# rgb_and_irdistance.net
KiCad netlist of a schematic drawn in EAGLE
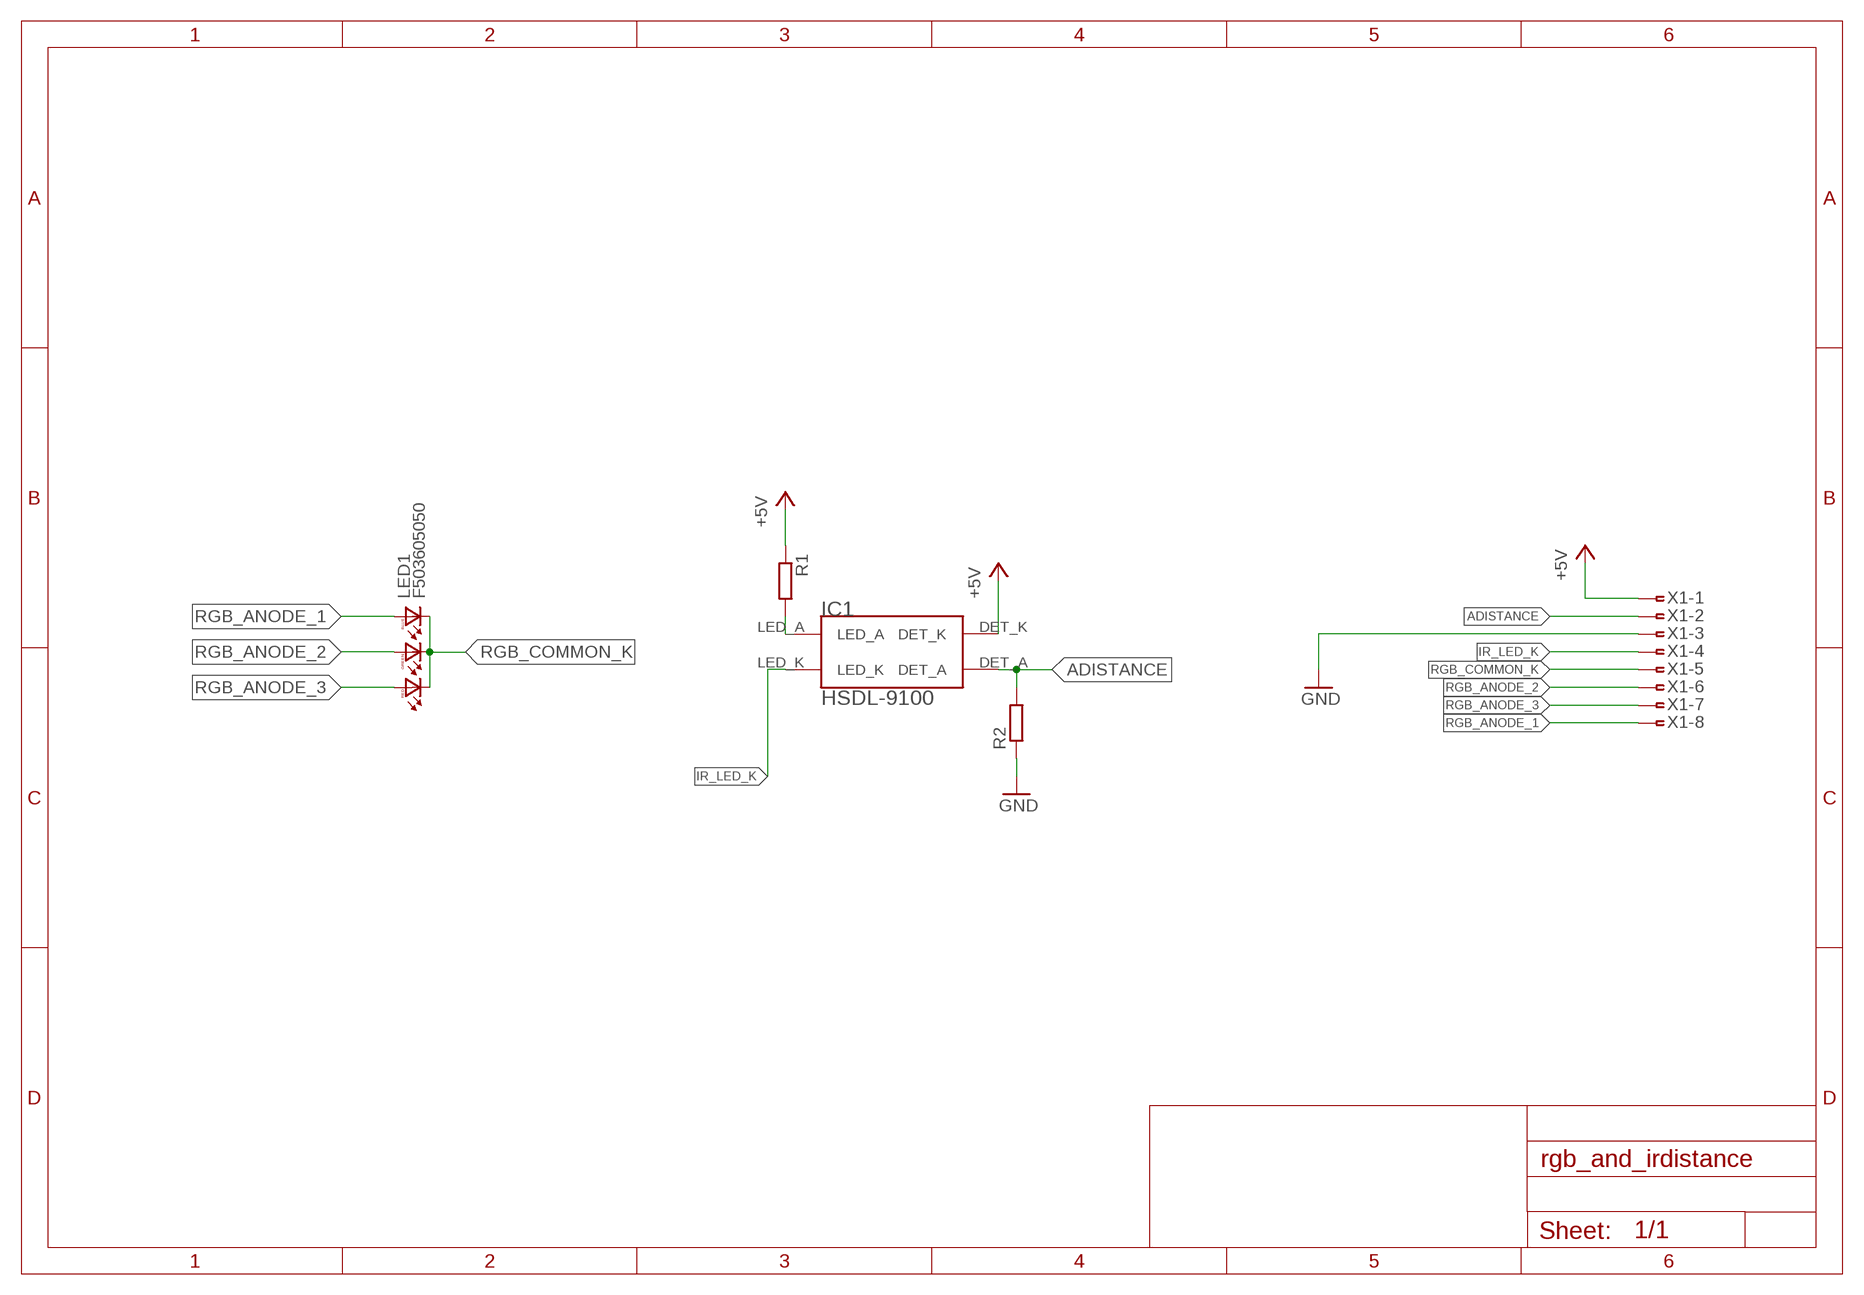
[diagram p0: schematic, sheet 1]

(export (version "E")
  (design (tool "Eeschema 10.0.6"))
  (components
    (comp (ref "IC1")
      (value "HSDL-9100")
      (footprint "eagle-import:HSDL-9100")
      (libsource (lib "eagle-import") (part "HSDL-9100"))
    )
    (comp (ref "LED1")
      (value "F503605050")
      (footprint "eagle-import:5050LED")
      (libsource (lib "eagle-import") (part "F503605050"))
    )
    (comp (ref "R1")
      (value "R-EU_M0805")
      (footprint "eagle-import:M0805")
      (libsource (lib "eagle-import") (part "R-EU_M0805"))
    )
    (comp (ref "R2")
      (value "R-EU_M0805")
      (footprint "eagle-import:M0805")
      (libsource (lib "eagle-import") (part "R-EU_M0805"))
    )
    (comp (ref "X1")
      (value "FTOP-8")
      (footprint "eagle-import:FTOP-8")
      (libsource (lib "eagle-import") (part "FTOP-8"))
    )
  )
  (nets
    (net (code "1") (name "+5V") (class "Default")
      (node (ref "IC1") (pin "DET_K") (pinfunction "DET_K_DET_K") (pintype "bidirectional"))
      (node (ref "R1") (pin "1") (pinfunction "1_1") (pintype "passive"))
      (node (ref "X1") (pin "1") (pinfunction "1_1") (pintype "passive"))
    )
    (net (code "2") (name "ADISTANCE") (class "Default")
      (node (ref "IC1") (pin "DET_A") (pinfunction "DET_A_DET_A") (pintype "bidirectional"))
      (node (ref "R2") (pin "2") (pinfunction "2_2") (pintype "passive"))
      (node (ref "X1") (pin "2") (pinfunction "1_2") (pintype "passive"))
    )
    (net (code "3") (name "GND") (class "Default")
      (node (ref "R2") (pin "1") (pinfunction "1_1") (pintype "passive"))
      (node (ref "X1") (pin "3") (pinfunction "1_3") (pintype "passive"))
    )
    (net (code "4") (name "IR_LED_K") (class "Default")
      (node (ref "IC1") (pin "LED_K") (pinfunction "LED_K_LED_K") (pintype "bidirectional"))
      (node (ref "X1") (pin "4") (pinfunction "1_4") (pintype "passive"))
    )
    (net (code "5") (name "Net-(IC1-PadLED_A)") (class "Default")
      (node (ref "IC1") (pin "LED_A") (pinfunction "LED_A_LED_A") (pintype "bidirectional"))
      (node (ref "R1") (pin "2") (pinfunction "2_2") (pintype "passive"))
    )
    (net (code "6") (name "RGB_ANODE_1") (class "Default")
      (node (ref "LED1") (pin "B1") (pinfunction "BA_B1") (pintype "passive"))
      (node (ref "X1") (pin "8") (pinfunction "1_8") (pintype "passive"))
    )
    (net (code "7") (name "RGB_ANODE_2") (class "Default")
      (node (ref "LED1") (pin "G1") (pinfunction "GA_G1") (pintype "passive"))
      (node (ref "X1") (pin "6") (pinfunction "1_6") (pintype "passive"))
    )
    (net (code "8") (name "RGB_ANODE_3") (class "Default")
      (node (ref "LED1") (pin "R1") (pinfunction "RA_R1") (pintype "passive"))
      (node (ref "X1") (pin "7") (pinfunction "1_7") (pintype "passive"))
    )
    (net (code "9") (name "RGB_COMMON_K") (class "Default")
      (node (ref "LED1") (pin "B2") (pinfunction "BC_B2") (pintype "passive"))
      (node (ref "LED1") (pin "G2") (pinfunction "GC_G2") (pintype "passive"))
      (node (ref "LED1") (pin "R2") (pinfunction "RC_R2") (pintype "passive"))
      (node (ref "X1") (pin "5") (pinfunction "1_5") (pintype "passive"))
    )
  )
)
